# mod.net
KiCad netlist of a schematic drawn in EAGLE
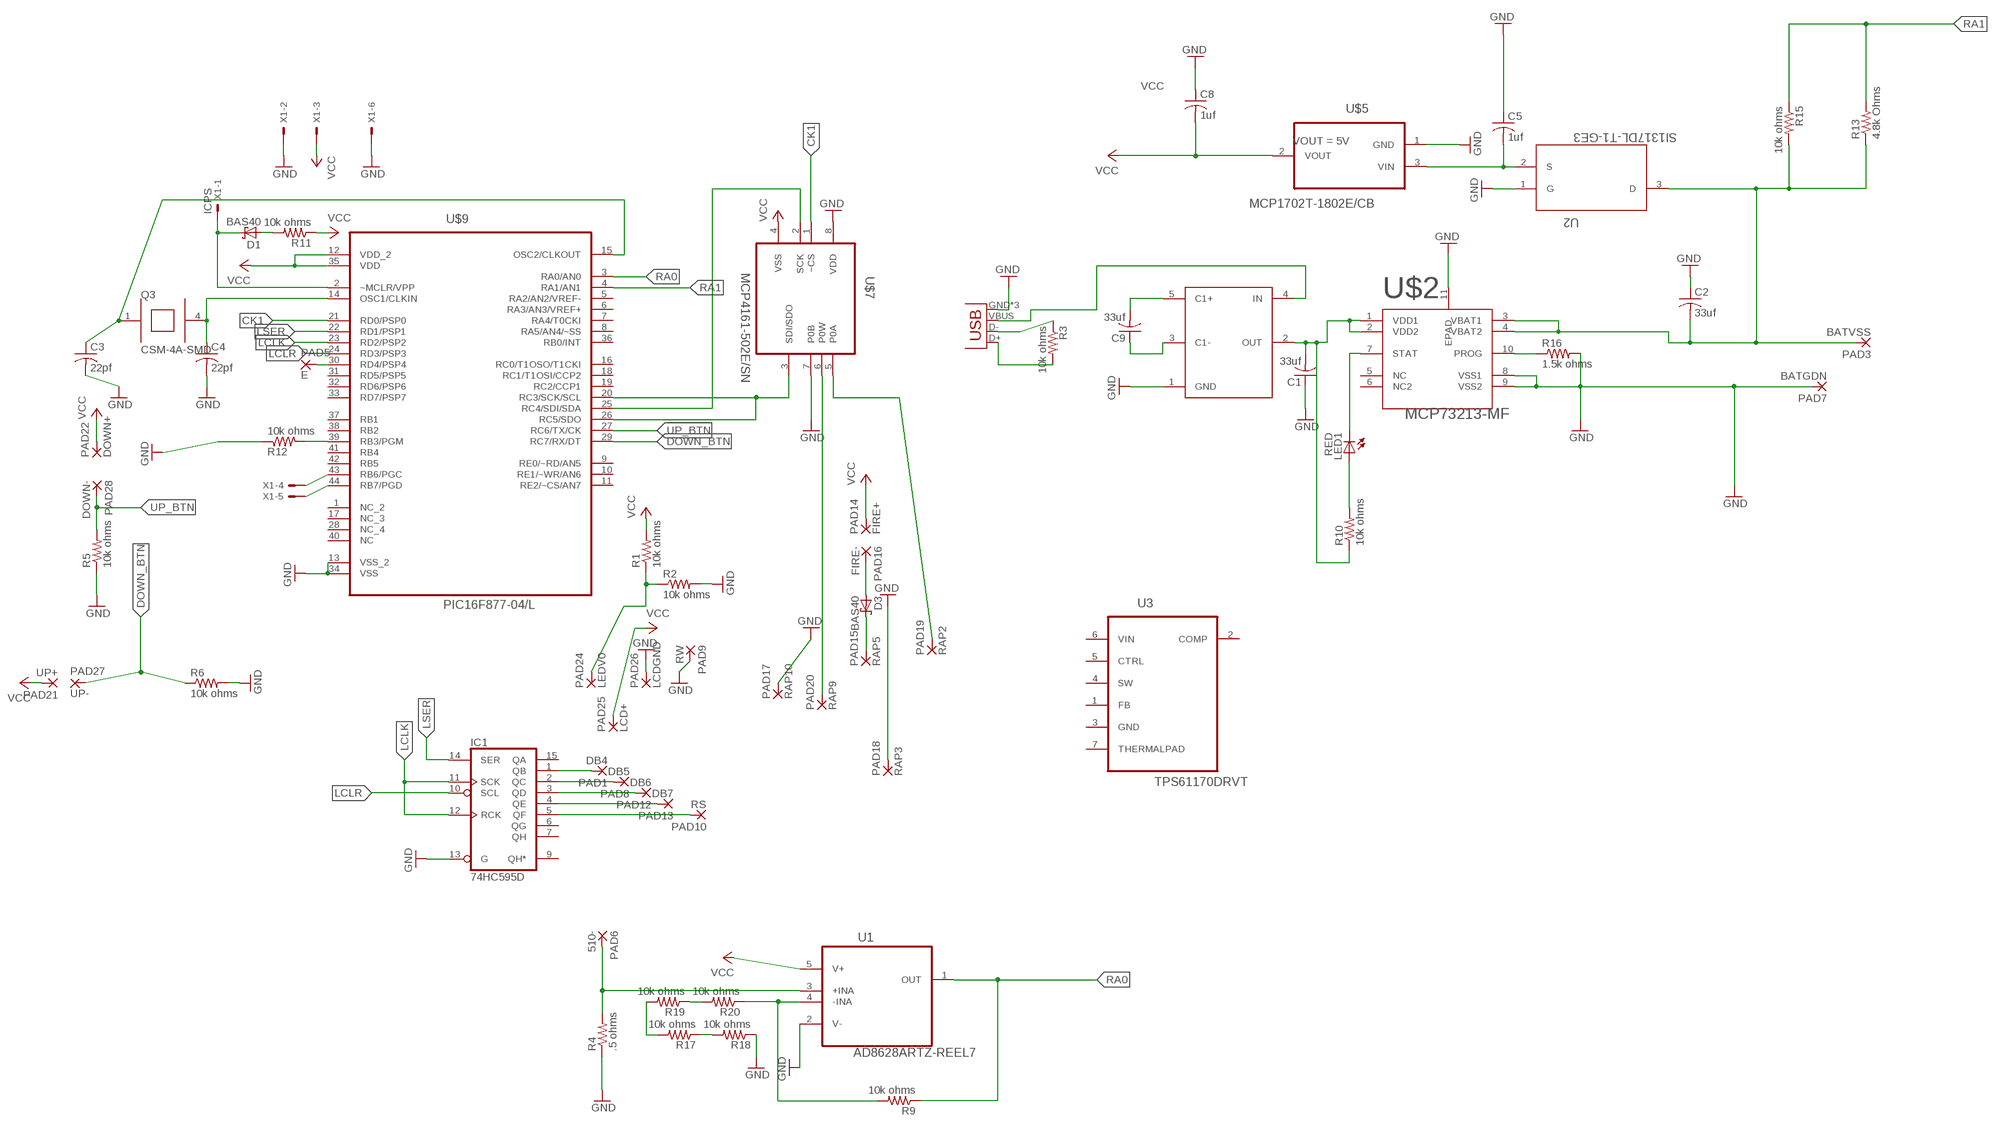
[diagram p0: schematic, sheet 1]

(export (version "E")
  (design (tool "Eeschema 10.0.6"))
  (components
    (comp (ref "C1")
      (value "33uf")
      (footprint "eagle-import:C0805")
      (fields (field (name "MPN") "RC0805JR-1347KL"))
      (libsource (lib "eagle-import") (part "C-USC0805"))
    )
    (comp (ref "C2")
      (value "33uf")
      (footprint "eagle-import:C0805")
      (fields (field (name "MPN") "RC0805JR-1347KL"))
      (libsource (lib "eagle-import") (part "C-USC0805"))
    )
    (comp (ref "C3")
      (value "22pf")
      (footprint "eagle-import:C0805")
      (fields (field (name "MPN") "MC0805N220J501CT"))
      (libsource (lib "eagle-import") (part "C-USC0805"))
    )
    (comp (ref "C4")
      (value "22pf")
      (footprint "eagle-import:C0805")
      (fields (field (name "MPN") "MC0805N220J501CT"))
      (libsource (lib "eagle-import") (part "C-USC0805"))
    )
    (comp (ref "C5")
      (value "1uf")
      (footprint "eagle-import:C0805")
      (fields (field (name "MPN") "RC0805JR-1347KL"))
      (libsource (lib "eagle-import") (part "C-USC0805"))
    )
    (comp (ref "C8")
      (value "1uf")
      (footprint "eagle-import:C0805")
      (fields (field (name "MPN") "RC0805JR-1347KL"))
      (libsource (lib "eagle-import") (part "C-USC0805"))
    )
    (comp (ref "C9")
      (value "33uf")
      (footprint "eagle-import:C0805")
      (fields (field (name "MPN") "RC0805JR-1347KL"))
      (libsource (lib "eagle-import") (part "C-USC0805"))
    )
    (comp (ref "D1")
      (value "BAS40")
      (footprint "eagle-import:SOT23")
      (libsource (lib "eagle-import") (part "BAS40"))
    )
    (comp (ref "D3")
      (value "BAS40")
      (footprint "eagle-import:SOT23")
      (libsource (lib "eagle-import") (part "BAS40"))
    )
    (comp (ref "IC1")
      (value "74HC595D")
      (footprint "eagle-import:SO16")
      (libsource (lib "eagle-import") (part "74595DHC"))
    )
    (comp (ref "LED1")
      (value "RED")
      (footprint "eagle-import:CHIPLED_1206")
      (libsource (lib "eagle-import") (part "LEDCHIPLED_1206"))
    )
    (comp (ref "PAD1")
      (value "DB4")
      (footprint "eagle-import:SMD1,27-2,54")
      (libsource (lib "eagle-import") (part "WIREPADSMD1,27-254"))
    )
    (comp (ref "PAD3")
      (value "BATVSS")
      (footprint "eagle-import:SMD1,27-2,54")
      (libsource (lib "eagle-import") (part "WIREPADSMD1,27-254"))
    )
    (comp (ref "PAD5")
      (value "E")
      (footprint "eagle-import:SMD1,27-2,54")
      (libsource (lib "eagle-import") (part "WIREPADSMD1,27-254"))
    )
    (comp (ref "PAD6")
      (value "510-")
      (footprint "eagle-import:SMD1,27-2,54")
      (libsource (lib "eagle-import") (part "WIREPADSMD1,27-254"))
    )
    (comp (ref "PAD7")
      (value "BATGDN")
      (footprint "eagle-import:SMD1,27-2,54")
      (libsource (lib "eagle-import") (part "WIREPADSMD1,27-254"))
    )
    (comp (ref "PAD8")
      (value "DB5")
      (footprint "eagle-import:SMD1,27-2,54")
      (libsource (lib "eagle-import") (part "WIREPADSMD1,27-254"))
    )
    (comp (ref "PAD9")
      (value "RW")
      (footprint "eagle-import:SMD1,27-2,54")
      (libsource (lib "eagle-import") (part "WIREPADSMD1,27-254"))
    )
    (comp (ref "PAD10")
      (value "RS")
      (footprint "eagle-import:SMD1,27-2,54")
      (libsource (lib "eagle-import") (part "WIREPADSMD1,27-254"))
    )
    (comp (ref "PAD12")
      (value "DB6")
      (footprint "eagle-import:SMD1,27-2,54")
      (libsource (lib "eagle-import") (part "WIREPADSMD1,27-254"))
    )
    (comp (ref "PAD13")
      (value "DB7")
      (footprint "eagle-import:SMD1,27-2,54")
      (libsource (lib "eagle-import") (part "WIREPADSMD1,27-254"))
    )
    (comp (ref "PAD14")
      (value "FIRE+")
      (footprint "eagle-import:SMD1,27-2,54")
      (libsource (lib "eagle-import") (part "WIREPADSMD1,27-254"))
    )
    (comp (ref "PAD15")
      (value "RAP5")
      (footprint "eagle-import:SMD1,27-2,54")
      (libsource (lib "eagle-import") (part "WIREPADSMD1,27-254"))
    )
    (comp (ref "PAD16")
      (value "FIRE-")
      (footprint "eagle-import:SMD1,27-2,54")
      (libsource (lib "eagle-import") (part "WIREPADSMD1,27-254"))
    )
    (comp (ref "PAD17")
      (value "RAP10")
      (footprint "eagle-import:SMD1,27-2,54")
      (libsource (lib "eagle-import") (part "WIREPADSMD1,27-254"))
    )
    (comp (ref "PAD18")
      (value "RAP3")
      (footprint "eagle-import:SMD1,27-2,54")
      (libsource (lib "eagle-import") (part "WIREPADSMD1,27-254"))
    )
    (comp (ref "PAD19")
      (value "RAP2")
      (footprint "eagle-import:SMD1,27-2,54")
      (libsource (lib "eagle-import") (part "WIREPADSMD1,27-254"))
    )
    (comp (ref "PAD20")
      (value "RAP9")
      (footprint "eagle-import:SMD1,27-2,54")
      (libsource (lib "eagle-import") (part "WIREPADSMD1,27-254"))
    )
    (comp (ref "PAD21")
      (value "UP+")
      (footprint "eagle-import:SMD1,27-2,54")
      (libsource (lib "eagle-import") (part "WIREPADSMD1,27-254"))
    )
    (comp (ref "PAD22")
      (value "DOWN+")
      (footprint "eagle-import:SMD1,27-2,54")
      (libsource (lib "eagle-import") (part "WIREPADSMD1,27-254"))
    )
    (comp (ref "PAD24")
      (value "LEDV0")
      (footprint "eagle-import:SMD1,27-2,54")
      (libsource (lib "eagle-import") (part "WIREPADSMD1,27-254"))
    )
    (comp (ref "PAD25")
      (value "LCD+")
      (footprint "eagle-import:SMD1,27-2,54")
      (libsource (lib "eagle-import") (part "WIREPADSMD1,27-254"))
    )
    (comp (ref "PAD26")
      (value "LCDGND")
      (footprint "eagle-import:SMD1,27-2,54")
      (libsource (lib "eagle-import") (part "WIREPADSMD1,27-254"))
    )
    (comp (ref "PAD27")
      (value "UP-")
      (footprint "eagle-import:SMD1,27-2,54")
      (libsource (lib "eagle-import") (part "WIREPADSMD1,27-254"))
    )
    (comp (ref "PAD28")
      (value "DOWN-")
      (footprint "eagle-import:SMD1,27-2,54")
      (libsource (lib "eagle-import") (part "WIREPADSMD1,27-254"))
    )
    (comp (ref "Q3")
      (value "CSM-4A-SMD")
      (footprint "eagle-import:HC49_US")
      (libsource (lib "eagle-import") (part "CSM-4A-SMD"))
    )
    (comp (ref "R1")
      (value "10k ohms")
      (footprint "eagle-import:R0805")
      (fields (field (name "MPN") "CRCW080510K0FKEB"))
      (libsource (lib "eagle-import") (part "R-US_R0805"))
    )
    (comp (ref "R2")
      (value "10k ohms")
      (footprint "eagle-import:R0805")
      (fields (field (name "MPN") "CRCW080510K0FKEB"))
      (libsource (lib "eagle-import") (part "R-US_R0805"))
    )
    (comp (ref "R3")
      (value "10k ohms")
      (footprint "eagle-import:R0805")
      (fields (field (name "MPN") "CRCW0805220RJNEA"))
      (libsource (lib "eagle-import") (part "R-US_R0805"))
    )
    (comp (ref "R4")
      (value ".5 ohms")
      (footprint "eagle-import:R0805")
      (fields (field (name "MPN") "CRCW080510K0FKEB"))
      (libsource (lib "eagle-import") (part "R-US_R0805"))
    )
    (comp (ref "R5")
      (value "10k ohms")
      (footprint "eagle-import:R0805")
      (fields (field (name "MPN") "CRCW080510K0FKEB"))
      (libsource (lib "eagle-import") (part "R-US_R0805"))
    )
    (comp (ref "R6")
      (value "10k ohms")
      (footprint "eagle-import:R0805")
      (fields (field (name "MPN") "CRCW080510K0FKEB"))
      (libsource (lib "eagle-import") (part "R-US_R0805"))
    )
    (comp (ref "R9")
      (value "10k ohms")
      (footprint "eagle-import:R0805")
      (fields (field (name "MPN") "CRCW080510K0FKEB"))
      (libsource (lib "eagle-import") (part "R-US_R0805"))
    )
    (comp (ref "R10")
      (value "10k ohms")
      (footprint "eagle-import:R0805")
      (fields (field (name "MPN") "CRCW0805220RJNEA"))
      (libsource (lib "eagle-import") (part "R-US_R0805"))
    )
    (comp (ref "R11")
      (value "10k ohms")
      (footprint "eagle-import:R0805")
      (fields (field (name "MPN") "CRCW080510K0FKEB"))
      (libsource (lib "eagle-import") (part "R-US_R0805"))
    )
    (comp (ref "R12")
      (value "10k ohms")
      (footprint "eagle-import:R0805")
      (fields (field (name "MPN") "CRCW080510K0FKEB"))
      (libsource (lib "eagle-import") (part "R-US_R0805"))
    )
    (comp (ref "R13")
      (value "4.8k Ohms")
      (footprint "eagle-import:R0805")
      (fields (field (name "MPN") "CRCW080510K0FKEB"))
      (libsource (lib "eagle-import") (part "R-US_R0805"))
    )
    (comp (ref "R15")
      (value "10k ohms")
      (footprint "eagle-import:R0805")
      (fields (field (name "MPN") "CRCW080510K0FKEB"))
      (libsource (lib "eagle-import") (part "R-US_R0805"))
    )
    (comp (ref "R16")
      (value "1.5k ohms")
      (footprint "eagle-import:R0805")
      (fields (field (name "MPN") "CRCW080510K0FKEB"))
      (libsource (lib "eagle-import") (part "R-US_R0805"))
    )
    (comp (ref "R17")
      (value "10k ohms")
      (footprint "eagle-import:R0805")
      (fields (field (name "MPN") "CRCW080510K0FKEB"))
      (libsource (lib "eagle-import") (part "R-US_R0805"))
    )
    (comp (ref "R18")
      (value "10k ohms")
      (footprint "eagle-import:R0805")
      (fields (field (name "MPN") "CRCW080510K0FKEB"))
      (libsource (lib "eagle-import") (part "R-US_R0805"))
    )
    (comp (ref "R19")
      (value "10k ohms")
      (footprint "eagle-import:R0805")
      (fields (field (name "MPN") "CRCW080510K0FKEB"))
      (libsource (lib "eagle-import") (part "R-US_R0805"))
    )
    (comp (ref "R20")
      (value "10k ohms")
      (footprint "eagle-import:R0805")
      (fields (field (name "MPN") "CRCW080510K0FKEB"))
      (libsource (lib "eagle-import") (part "R-US_R0805"))
    )
    (comp (ref "U$2")
      (value "MCP73213-MF")
      (footprint "eagle-import:10-DFN")
      (libsource (lib "eagle-import") (part "MCP73213-MF"))
    )
    (comp (ref "U$3")
      (value "MAX1683-5-SOT23")
      (footprint "eagle-import:SOT23-1")
      (libsource (lib "eagle-import") (part "MAX1683-5-SOT23"))
    )
    (comp (ref "U$5")
      (value "MCP1702T-1802E/CB")
      (footprint "eagle-import:SOT95P300X145-3N")
      (fields (field (name "VOUT") "5V"))
      (libsource (lib "eagle-import") (part "MCP1702T-1802E/CB"))
    )
    (comp (ref "U$7")
      (value "MCP4161-502E/SN")
      (footprint "eagle-import:SOIC127P600X175-8N")
      (libsource (lib "eagle-import") (part "MCP4161-502E/SN"))
    )
    (comp (ref "U$9")
      (value "PIC16F877-04/L")
      (footprint "eagle-import:PLCC127P1752X1752X457-44N")
      (fields (field (name "MF") "MICROCHIP"))
      (libsource (lib "eagle-import") (part "PIC16F877-04/L"))
    )
    (comp (ref "U1")
      (value "AD8628ARTZ-REEL7")
      (footprint "eagle-import:SOT95P290X145-5N")
      (libsource (lib "eagle-import") (part "AD8628ARTZ-REEL7"))
    )
    (comp (ref "U2")
      (value "SI1317DL-T1-GE3")
      (footprint "eagle-import:SOT65P210X110-3N")
      (libsource (lib "eagle-import") (part "SI1317DL-T1-GE3"))
    )
    (comp (ref "U3")
      (value "TPS61170DRVT")
      (footprint "eagle-import:SON65P210X210X80-7N")
      (libsource (lib "eagle-import") (part "TPS61170DRVT"))
    )
    (comp (ref "X1")
      (value "ICPS")
      (footprint "eagle-import:22-23-2061")
      (fields (field (name "MF") "MOLEX") (field (name "MPN") "22-23-2061"))
      (libsource (lib "eagle-import") (part "22-23-2061"))
    )
    (comp (ref "X2")
      (value "USB-MICROB")
      (footprint "eagle-import:USB-MICROB")
      (libsource (lib "eagle-import") (part "USB-MICROB"))
    )
  )
  (nets
    (net (code "1") (name "/VIN") (class "Default")
      (node (ref "U3") (pin "6") (pinfunction "VIN_6") (pintype "power_in"))
    )
    (net (code "2") (name "CK1") (class "Default")
      (node (ref "U$7") (pin "1") (pinfunction "~{CS}_1") (pintype "input"))
      (node (ref "U$9") (pin "21") (pinfunction "RD0/PSP0_21") (pintype "bidirectional"))
    )
    (net (code "3") (name "DOWN_BTN") (class "Default")
      (node (ref "PAD27") (pin "1") (pinfunction "P_1") (pintype "passive"))
      (node (ref "R6") (pin "1") (pinfunction "1_1") (pintype "passive"))
      (node (ref "U$9") (pin "29") (pinfunction "RC7/RX/DT_29") (pintype "bidirectional"))
    )
    (net (code "4") (name "GND") (class "Default")
      (node (ref "C1") (pin "1") (pinfunction "1_1") (pintype "passive"))
      (node (ref "C2") (pin "1") (pinfunction "1_1") (pintype "passive"))
      (node (ref "C3") (pin "2") (pinfunction "2_2") (pintype "passive"))
      (node (ref "C4") (pin "2") (pinfunction "2_2") (pintype "passive"))
      (node (ref "C5") (pin "1") (pinfunction "1_1") (pintype "passive"))
      (node (ref "C8") (pin "1") (pinfunction "1_1") (pintype "passive"))
      (node (ref "IC1") (pin "13") (pinfunction "G_13") (pintype "input"))
      (node (ref "PAD17") (pin "1") (pinfunction "P_1") (pintype "passive"))
      (node (ref "PAD18") (pin "1") (pinfunction "P_1") (pintype "passive"))
      (node (ref "PAD26") (pin "1") (pinfunction "P_1") (pintype "passive"))
      (node (ref "PAD7") (pin "1") (pinfunction "P_1") (pintype "passive"))
      (node (ref "PAD9") (pin "1") (pinfunction "P_1") (pintype "passive"))
      (node (ref "R12") (pin "1") (pinfunction "1_1") (pintype "passive"))
      (node (ref "R16") (pin "2") (pinfunction "2_2") (pintype "passive"))
      (node (ref "R18") (pin "1") (pinfunction "1_1") (pintype "passive"))
      (node (ref "R2") (pin "2") (pinfunction "2_2") (pintype "passive"))
      (node (ref "R4") (pin "1") (pinfunction "1_1") (pintype "passive"))
      (node (ref "R5") (pin "1") (pinfunction "1_1") (pintype "passive"))
      (node (ref "R6") (pin "2") (pinfunction "2_2") (pintype "passive"))
      (node (ref "U$2") (pin "11") (pinfunction "EPAD_11") (pintype "bidirectional"))
      (node (ref "U$2") (pin "8") (pinfunction "VSS1_8") (pintype "bidirectional"))
      (node (ref "U$2") (pin "9") (pinfunction "VSS2_9") (pintype "bidirectional"))
      (node (ref "U$3") (pin "1") (pinfunction "GND_1") (pintype "bidirectional"))
      (node (ref "U$5") (pin "1") (pinfunction "GND_1") (pintype "passive"))
      (node (ref "U$7") (pin "7") (pinfunction "P0B_7") (pintype "passive"))
      (node (ref "U$7") (pin "8") (pinfunction "VDD_8") (pintype "power_in"))
      (node (ref "U$9") (pin "13") (pinfunction "VSS_2_13") (pintype "power_in"))
      (node (ref "U$9") (pin "34") (pinfunction "VSS_34") (pintype "power_in"))
      (node (ref "U1") (pin "2") (pinfunction "V-_2") (pintype "power_in"))
      (node (ref "U2") (pin "1") (pinfunction "G_1") (pintype "passive"))
      (node (ref "X1") (pin "2") (pinfunction "S_2") (pintype "passive"))
      (node (ref "X1") (pin "6") (pinfunction "S_6") (pintype "passive"))
      (node (ref "X2") (pin "GND") (pinfunction "GND_GND") (pintype "bidirectional"))
      (node (ref "X2") (pin "MT1") (pinfunction "GND_MT1") (pintype "bidirectional"))
      (node (ref "X2") (pin "MT2") (pinfunction "GND_MT2") (pintype "bidirectional"))
    )
    (net (code "5") (name "LCLK") (class "Default")
      (node (ref "IC1") (pin "11") (pinfunction "SCK_11") (pintype "input"))
      (node (ref "IC1") (pin "12") (pinfunction "RCK_12") (pintype "input"))
      (node (ref "U$9") (pin "23") (pinfunction "RD2/PSP2_23") (pintype "bidirectional"))
    )
    (net (code "6") (name "LCLR") (class "Default")
      (node (ref "IC1") (pin "10") (pinfunction "SCL_10") (pintype "input"))
      (node (ref "U$9") (pin "24") (pinfunction "RD3/PSP3_24") (pintype "bidirectional"))
    )
    (net (code "7") (name "LSER") (class "Default")
      (node (ref "IC1") (pin "14") (pinfunction "SER_14") (pintype "input"))
      (node (ref "U$9") (pin "22") (pinfunction "RD1/PSP1_22") (pintype "bidirectional"))
    )
    (net (code "8") (name "Net-(D1-A)") (class "Default")
      (node (ref "D1") (pin "1") (pinfunction "A_1") (pintype "passive"))
      (node (ref "R11") (pin "2") (pinfunction "2_2") (pintype "passive"))
    )
    (net (code "9") (name "Net-(D1-C)") (class "Default")
      (node (ref "D1") (pin "3") (pinfunction "C_3") (pintype "passive"))
      (node (ref "U$9") (pin "2") (pinfunction "~{MCLR/VPP}_2") (pintype "input"))
      (node (ref "X1") (pin "1") (pinfunction "S_1") (pintype "passive"))
    )
    (net (code "10") (name "Net-(D3-A)") (class "Default")
      (node (ref "D3") (pin "1") (pinfunction "A_1") (pintype "passive"))
      (node (ref "PAD16") (pin "1") (pinfunction "P_1") (pintype "passive"))
    )
    (net (code "11") (name "Net-(D3-C)") (class "Default")
      (node (ref "D3") (pin "3") (pinfunction "C_3") (pintype "passive"))
      (node (ref "PAD15") (pin "1") (pinfunction "P_1") (pintype "passive"))
    )
    (net (code "12") (name "Net-(IC1A-QB)") (class "Default")
      (node (ref "IC1") (pin "1") (pinfunction "QB_1") (pintype "tri_state"))
      (node (ref "PAD1") (pin "1") (pinfunction "P_1") (pintype "passive"))
    )
    (net (code "13") (name "Net-(IC1A-QC)") (class "Default")
      (node (ref "IC1") (pin "2") (pinfunction "QC_2") (pintype "tri_state"))
      (node (ref "PAD8") (pin "1") (pinfunction "P_1") (pintype "passive"))
    )
    (net (code "14") (name "Net-(IC1A-QD)") (class "Default")
      (node (ref "IC1") (pin "3") (pinfunction "QD_3") (pintype "tri_state"))
      (node (ref "PAD12") (pin "1") (pinfunction "P_1") (pintype "passive"))
    )
    (net (code "15") (name "Net-(IC1A-QE)") (class "Default")
      (node (ref "IC1") (pin "4") (pinfunction "QE_4") (pintype "tri_state"))
      (node (ref "PAD13") (pin "1") (pinfunction "P_1") (pintype "passive"))
    )
    (net (code "16") (name "Net-(IC1A-QF)") (class "Default")
      (node (ref "IC1") (pin "5") (pinfunction "QF_5") (pintype "tri_state"))
      (node (ref "PAD10") (pin "1") (pinfunction "P_1") (pintype "passive"))
    )
    (net (code "17") (name "Net-(LED1-PadA)") (class "Default")
      (node (ref "LED1") (pin "A") (pinfunction "A_A") (pintype "passive"))
      (node (ref "R10") (pin "2") (pinfunction "2_2") (pintype "passive"))
    )
    (net (code "18") (name "Net-(PAD3-P)") (class "Default")
      (node (ref "C2") (pin "2") (pinfunction "2_2") (pintype "passive"))
      (node (ref "PAD3") (pin "1") (pinfunction "P_1") (pintype "passive"))
      (node (ref "R13") (pin "1") (pinfunction "1_1") (pintype "passive"))
      (node (ref "R15") (pin "2") (pinfunction "2_2") (pintype "passive"))
      (node (ref "U$2") (pin "3") (pinfunction "VBAT1_3") (pintype "bidirectional"))
      (node (ref "U$2") (pin "4") (pinfunction "VBAT2_4") (pintype "bidirectional"))
      (node (ref "U2") (pin "3") (pinfunction "D_3") (pintype "passive"))
    )
    (net (code "19") (name "Net-(PAD5-P)") (class "Default")
      (node (ref "PAD5") (pin "1") (pinfunction "P_1") (pintype "passive"))
      (node (ref "U$9") (pin "30") (pinfunction "RD4/PSP4_30") (pintype "bidirectional"))
    )
    (net (code "20") (name "Net-(PAD6-P)") (class "Default")
      (node (ref "PAD6") (pin "1") (pinfunction "P_1") (pintype "passive"))
      (node (ref "R4") (pin "2") (pinfunction "2_2") (pintype "passive"))
      (node (ref "U1") (pin "3") (pinfunction "+INA_3") (pintype "passive"))
    )
    (net (code "21") (name "Net-(PAD19-P)") (class "Default")
      (node (ref "PAD19") (pin "1") (pinfunction "P_1") (pintype "passive"))
      (node (ref "U$7") (pin "5") (pinfunction "P0A_5") (pintype "passive"))
    )
    (net (code "22") (name "Net-(PAD20-P)") (class "Default")
      (node (ref "PAD20") (pin "1") (pinfunction "P_1") (pintype "passive"))
      (node (ref "U$7") (pin "6") (pinfunction "P0W_6") (pintype "passive"))
    )
    (net (code "23") (name "Net-(PAD24-P)") (class "Default")
      (node (ref "PAD24") (pin "1") (pinfunction "P_1") (pintype "passive"))
      (node (ref "R1") (pin "1") (pinfunction "1_1") (pintype "passive"))
      (node (ref "R2") (pin "1") (pinfunction "1_1") (pintype "passive"))
    )
    (net (code "24") (name "Net-(Q3-2)") (class "Default")
      (node (ref "C4") (pin "1") (pinfunction "1_1") (pintype "passive"))
      (node (ref "Q3") (pin "4") (pinfunction "2_4") (pintype "bidirectional"))
      (node (ref "U$9") (pin "14") (pinfunction "OSC1/CLKIN_14") (pintype "input"))
    )
    (net (code "25") (name "Net-(R3-Pad1)") (class "Default")
      (node (ref "R3") (pin "1") (pinfunction "1_1") (pintype "passive"))
      (node (ref "X2") (pin "D-") (pinfunction "D-_D-") (pintype "bidirectional"))
    )
    (net (code "26") (name "Net-(R3-Pad2)") (class "Default")
      (node (ref "R3") (pin "2") (pinfunction "2_2") (pintype "passive"))
      (node (ref "X2") (pin "D+") (pinfunction "D+_D+") (pintype "bidirectional"))
    )
    (net (code "27") (name "Net-(R17-Pad1)") (class "Default")
      (node (ref "R17") (pin "1") (pinfunction "1_1") (pintype "passive"))
      (node (ref "R18") (pin "2") (pinfunction "2_2") (pintype "passive"))
    )
    (net (code "28") (name "Net-(R17-Pad2)") (class "Default")
      (node (ref "R17") (pin "2") (pinfunction "2_2") (pintype "passive"))
      (node (ref "R19") (pin "2") (pinfunction "2_2") (pintype "passive"))
    )
    (net (code "29") (name "Net-(R19-Pad1)") (class "Default")
      (node (ref "R19") (pin "1") (pinfunction "1_1") (pintype "passive"))
      (node (ref "R20") (pin "2") (pinfunction "2_2") (pintype "passive"))
    )
    (net (code "30") (name "Net-(U$2B-PROG)") (class "Default")
      (node (ref "R16") (pin "1") (pinfunction "1_1") (pintype "passive"))
      (node (ref "U$2") (pin "10") (pinfunction "PROG_10") (pintype "bidirectional"))
    )
    (net (code "31") (name "Net-(U$2B-STAT)") (class "Default")
      (node (ref "LED1") (pin "C") (pinfunction "C_C") (pintype "passive"))
      (node (ref "U$2") (pin "7") (pinfunction "STAT_7") (pintype "bidirectional"))
    )
    (net (code "32") (name "Net-(U$2B-VDD1)") (class "Default")
      (node (ref "C1") (pin "2") (pinfunction "2_2") (pintype "passive"))
      (node (ref "R10") (pin "1") (pinfunction "1_1") (pintype "passive"))
      (node (ref "U$2") (pin "1") (pinfunction "VDD1_1") (pintype "bidirectional"))
      (node (ref "U$2") (pin "2") (pinfunction "VDD2_2") (pintype "bidirectional"))
      (node (ref "U$3") (pin "2") (pinfunction "OUT_2") (pintype "bidirectional"))
    )
    (net (code "33") (name "Net-(U$3-C1+)") (class "Default")
      (node (ref "C9") (pin "2") (pinfunction "2_2") (pintype "passive"))
      (node (ref "U$3") (pin "5") (pinfunction "C1+_5") (pintype "bidirectional"))
    )
    (net (code "34") (name "Net-(U$3-C1-)") (class "Default")
      (node (ref "C9") (pin "1") (pinfunction "1_1") (pintype "passive"))
      (node (ref "U$3") (pin "3") (pinfunction "C1-_3") (pintype "bidirectional"))
    )
    (net (code "35") (name "Net-(U$3-IN)") (class "Default")
      (node (ref "U$3") (pin "4") (pinfunction "IN_4") (pintype "bidirectional"))
      (node (ref "X2") (pin "VBUS") (pinfunction "VBUS_VBUS") (pintype "bidirectional"))
    )
    (net (code "36") (name "Net-(U$5-VIN)") (class "Default")
      (node (ref "C5") (pin "2") (pinfunction "2_2") (pintype "passive"))
      (node (ref "U$5") (pin "3") (pinfunction "VIN_3") (pintype "power_in"))
      (node (ref "U2") (pin "2") (pinfunction "S_2") (pintype "passive"))
    )
    (net (code "37") (name "Net-(U$7-SCK)") (class "Default")
      (node (ref "U$7") (pin "2") (pinfunction "SCK_2") (pintype "input"))
      (node (ref "U$9") (pin "25") (pinfunction "RC4/SDI/SDA_25") (pintype "bidirectional"))
    )
    (net (code "38") (name "Net-(U$7-SDI{slash}SDO)") (class "Default")
      (node (ref "U$7") (pin "3") (pinfunction "SDI/SDO_3") (pintype "bidirectional"))
      (node (ref "U$9") (pin "20") (pinfunction "RC3/SCK/SCL_20") (pintype "bidirectional"))
      (node (ref "U$9") (pin "26") (pinfunction "RC5/SDO_26") (pintype "bidirectional"))
    )
    (net (code "39") (name "Net-(U$9-OSC2{slash}CLKOUT)") (class "Default")
      (node (ref "C3") (pin "1") (pinfunction "1_1") (pintype "passive"))
      (node (ref "Q3") (pin "1") (pinfunction "1_1") (pintype "bidirectional"))
      (node (ref "U$9") (pin "15") (pinfunction "OSC2/CLKOUT_15") (pintype "output"))
    )
    (net (code "40") (name "Net-(U$9-RB3{slash}PGM)") (class "Default")
      (node (ref "R12") (pin "2") (pinfunction "2_2") (pintype "passive"))
      (node (ref "U$9") (pin "39") (pinfunction "RB3/PGM_39") (pintype "bidirectional"))
    )
    (net (code "41") (name "Net-(U$9-RB6{slash}PGC)") (class "Default")
      (node (ref "U$9") (pin "43") (pinfunction "RB6/PGC_43") (pintype "bidirectional"))
      (node (ref "X1") (pin "4") (pinfunction "S_4") (pintype "passive"))
    )
    (net (code "42") (name "Net-(U$9-RB7{slash}PGD)") (class "Default")
      (node (ref "U$9") (pin "44") (pinfunction "RB7/PGD_44") (pintype "bidirectional"))
      (node (ref "X1") (pin "5") (pinfunction "S_5") (pintype "passive"))
    )
    (net (code "43") (name "Net-(U1--INA)") (class "Default")
      (node (ref "R20") (pin "1") (pinfunction "1_1") (pintype "passive"))
      (node (ref "R9") (pin "2") (pinfunction "2_2") (pintype "passive"))
      (node (ref "U1") (pin "4") (pinfunction "-INA_4") (pintype "passive"))
    )
    (net (code "44") (name "RA0") (class "Default")
      (node (ref "R9") (pin "1") (pinfunction "1_1") (pintype "passive"))
      (node (ref "U$9") (pin "3") (pinfunction "RA0/AN0_3") (pintype "bidirectional"))
      (node (ref "U1") (pin "1") (pinfunction "OUT_1") (pintype "passive"))
    )
    (net (code "45") (name "RA1") (class "Default")
      (node (ref "R13") (pin "2") (pinfunction "2_2") (pintype "passive"))
      (node (ref "R15") (pin "1") (pinfunction "1_1") (pintype "passive"))
      (node (ref "U$9") (pin "4") (pinfunction "RA1/AN1_4") (pintype "bidirectional"))
    )
    (net (code "46") (name "UP_BTN") (class "Default")
      (node (ref "PAD28") (pin "1") (pinfunction "P_1") (pintype "passive"))
      (node (ref "R5") (pin "2") (pinfunction "2_2") (pintype "passive"))
      (node (ref "U$9") (pin "27") (pinfunction "RC6/TX/CK_27") (pintype "bidirectional"))
    )
    (net (code "47") (name "VCC") (class "Default")
      (node (ref "C8") (pin "2") (pinfunction "2_2") (pintype "passive"))
      (node (ref "PAD14") (pin "1") (pinfunction "P_1") (pintype "passive"))
      (node (ref "PAD21") (pin "1") (pinfunction "P_1") (pintype "passive"))
      (node (ref "PAD22") (pin "1") (pinfunction "P_1") (pintype "passive"))
      (node (ref "PAD25") (pin "1") (pinfunction "P_1") (pintype "passive"))
      (node (ref "R1") (pin "2") (pinfunction "2_2") (pintype "passive"))
      (node (ref "R11") (pin "1") (pinfunction "1_1") (pintype "passive"))
      (node (ref "U$5") (pin "2") (pinfunction "VOUT_2") (pintype "output"))
      (node (ref "U$7") (pin "4") (pinfunction "VSS_4") (pintype "power_in"))
      (node (ref "U$9") (pin "12") (pinfunction "VDD_2_12") (pintype "power_in"))
      (node (ref "U$9") (pin "35") (pinfunction "VDD_35") (pintype "power_in"))
      (node (ref "U1") (pin "5") (pinfunction "V+_5") (pintype "power_in"))
      (node (ref "X1") (pin "3") (pinfunction "S_3") (pintype "passive"))
    )
    (net (code "48") (name "unconnected-(IC1A-QA-Pad15)") (class "Default")
      (node (ref "IC1") (pin "15") (pinfunction "QA_15") (pintype "tri_state"))
    )
    (net (code "49") (name "unconnected-(IC1A-QG-Pad6)") (class "Default")
      (node (ref "IC1") (pin "6") (pinfunction "QG_6") (pintype "tri_state"))
    )
    (net (code "50") (name "unconnected-(IC1A-QH*-Pad9)") (class "Default")
      (node (ref "IC1") (pin "9") (pinfunction "QH*_9") (pintype "tri_state"))
    )
    (net (code "51") (name "unconnected-(IC1A-QH-Pad7)") (class "Default")
      (node (ref "IC1") (pin "7") (pinfunction "QH_7") (pintype "tri_state"))
    )
    (net (code "52") (name "unconnected-(U$2B-NC-Pad5)") (class "Default")
      (node (ref "U$2") (pin "5") (pinfunction "NC_5") (pintype "bidirectional"))
    )
    (net (code "53") (name "unconnected-(U$2B-NC2-Pad6)") (class "Default")
      (node (ref "U$2") (pin "6") (pinfunction "NC2_6") (pintype "bidirectional"))
    )
    (net (code "54") (name "unconnected-(U$9-NC-Pad40)") (class "Default")
      (node (ref "U$9") (pin "40") (pinfunction "NC_40") (pintype "no_connect"))
    )
    (net (code "55") (name "unconnected-(U$9-NC_2-Pad1)") (class "Default")
      (node (ref "U$9") (pin "1") (pinfunction "NC_2_1") (pintype "no_connect"))
    )
    (net (code "56") (name "unconnected-(U$9-NC_3-Pad17)") (class "Default")
      (node (ref "U$9") (pin "17") (pinfunction "NC_3_17") (pintype "no_connect"))
    )
    (net (code "57") (name "unconnected-(U$9-NC_4-Pad28)") (class "Default")
      (node (ref "U$9") (pin "28") (pinfunction "NC_4_28") (pintype "no_connect"))
    )
    (net (code "58") (name "unconnected-(U$9-RA2{slash}AN2{slash}VREF--Pad5)") (class "Default")
      (node (ref "U$9") (pin "5") (pinfunction "RA2/AN2/VREF-_5") (pintype "bidirectional"))
    )
    (net (code "59") (name "unconnected-(U$9-RA3{slash}AN3{slash}VREF+-Pad6)") (class "Default")
      (node (ref "U$9") (pin "6") (pinfunction "RA3/AN3/VREF+_6") (pintype "bidirectional"))
    )
    (net (code "60") (name "unconnected-(U$9-RA4{slash}T0CKI-Pad7)") (class "Default")
      (node (ref "U$9") (pin "7") (pinfunction "RA4/T0CKI_7") (pintype "bidirectional"))
    )
    (net (code "61") (name "unconnected-(U$9-RA5{slash}AN4{slash}~{SS}-Pad8)") (class "Default")
      (node (ref "U$9") (pin "8") (pinfunction "RA5/AN4/~{SS}_8") (pintype "bidirectional"))
    )
    (net (code "62") (name "unconnected-(U$9-RB0{slash}INT-Pad36)") (class "Default")
      (node (ref "U$9") (pin "36") (pinfunction "RB0/INT_36") (pintype "bidirectional"))
    )
    (net (code "63") (name "unconnected-(U$9-RB1-Pad37)") (class "Default")
      (node (ref "U$9") (pin "37") (pinfunction "RB1_37") (pintype "bidirectional"))
    )
    (net (code "64") (name "unconnected-(U$9-RB2-Pad38)") (class "Default")
      (node (ref "U$9") (pin "38") (pinfunction "RB2_38") (pintype "bidirectional"))
    )
    (net (code "65") (name "unconnected-(U$9-RB4-Pad41)") (class "Default")
      (node (ref "U$9") (pin "41") (pinfunction "RB4_41") (pintype "bidirectional"))
    )
    (net (code "66") (name "unconnected-(U$9-RB5-Pad42)") (class "Default")
      (node (ref "U$9") (pin "42") (pinfunction "RB5_42") (pintype "bidirectional"))
    )
    (net (code "67") (name "unconnected-(U$9-RC0{slash}T1OSO{slash}T1CKI-Pad16)") (class "Default")
      (node (ref "U$9") (pin "16") (pinfunction "RC0/T1OSO/T1CKI_16") (pintype "bidirectional"))
    )
    (net (code "68") (name "unconnected-(U$9-RC1{slash}T1OSI{slash}CCP2-Pad18)") (class "Default")
      (node (ref "U$9") (pin "18") (pinfunction "RC1/T1OSI/CCP2_18") (pintype "bidirectional"))
    )
    (net (code "69") (name "unconnected-(U$9-RC2{slash}CCP1-Pad19)") (class "Default")
      (node (ref "U$9") (pin "19") (pinfunction "RC2/CCP1_19") (pintype "bidirectional"))
    )
    (net (code "70") (name "unconnected-(U$9-RD5{slash}PSP5-Pad31)") (class "Default")
      (node (ref "U$9") (pin "31") (pinfunction "RD5/PSP5_31") (pintype "bidirectional"))
    )
    (net (code "71") (name "unconnected-(U$9-RD6{slash}PSP6-Pad32)") (class "Default")
      (node (ref "U$9") (pin "32") (pinfunction "RD6/PSP6_32") (pintype "bidirectional"))
    )
    (net (code "72") (name "unconnected-(U$9-RD7{slash}PSP7-Pad33)") (class "Default")
      (node (ref "U$9") (pin "33") (pinfunction "RD7/PSP7_33") (pintype "bidirectional"))
    )
    (net (code "73") (name "unconnected-(U$9-RE0{slash}~{RD{slash}AN5}-Pad9)") (class "Default")
      (node (ref "U$9") (pin "9") (pinfunction "RE0/~{RD/AN5}_9") (pintype "bidirectional"))
    )
    (net (code "74") (name "unconnected-(U$9-RE1{slash}~{WR{slash}AN6}-Pad10)") (class "Default")
      (node (ref "U$9") (pin "10") (pinfunction "RE1/~{WR/AN6}_10") (pintype "bidirectional"))
    )
    (net (code "75") (name "unconnected-(U$9-RE2{slash}~{CS{slash}AN7}-Pad11)") (class "Default")
      (node (ref "U$9") (pin "11") (pinfunction "RE2/~{CS/AN7}_11") (pintype "bidirectional"))
    )
    (net (code "76") (name "unconnected-(U3-COMP-Pad2)") (class "Default")
      (node (ref "U3") (pin "2") (pinfunction "COMP_2") (pintype "output"))
    )
    (net (code "77") (name "unconnected-(U3-CTRL-Pad5)") (class "Default")
      (node (ref "U3") (pin "5") (pinfunction "CTRL_5") (pintype "input"))
    )
    (net (code "78") (name "unconnected-(U3-FB-Pad1)") (class "Default")
      (node (ref "U3") (pin "1") (pinfunction "FB_1") (pintype "input"))
    )
    (net (code "79") (name "unconnected-(U3-GND-Pad3)") (class "Default")
      (node (ref "U3") (pin "3") (pinfunction "GND_3") (pintype "passive"))
    )
    (net (code "80") (name "unconnected-(U3-SW-Pad4)") (class "Default")
      (node (ref "U3") (pin "4") (pinfunction "SW_4") (pintype "input"))
    )
    (net (code "81") (name "unconnected-(U3-THERMALPAD-Pad7)") (class "Default")
      (node (ref "U3") (pin "7") (pinfunction "THERMALPAD_7") (pintype "passive"))
    )
  )
)
